# schematic.net
KiCad netlist of a schematic drawn in Altium Designer
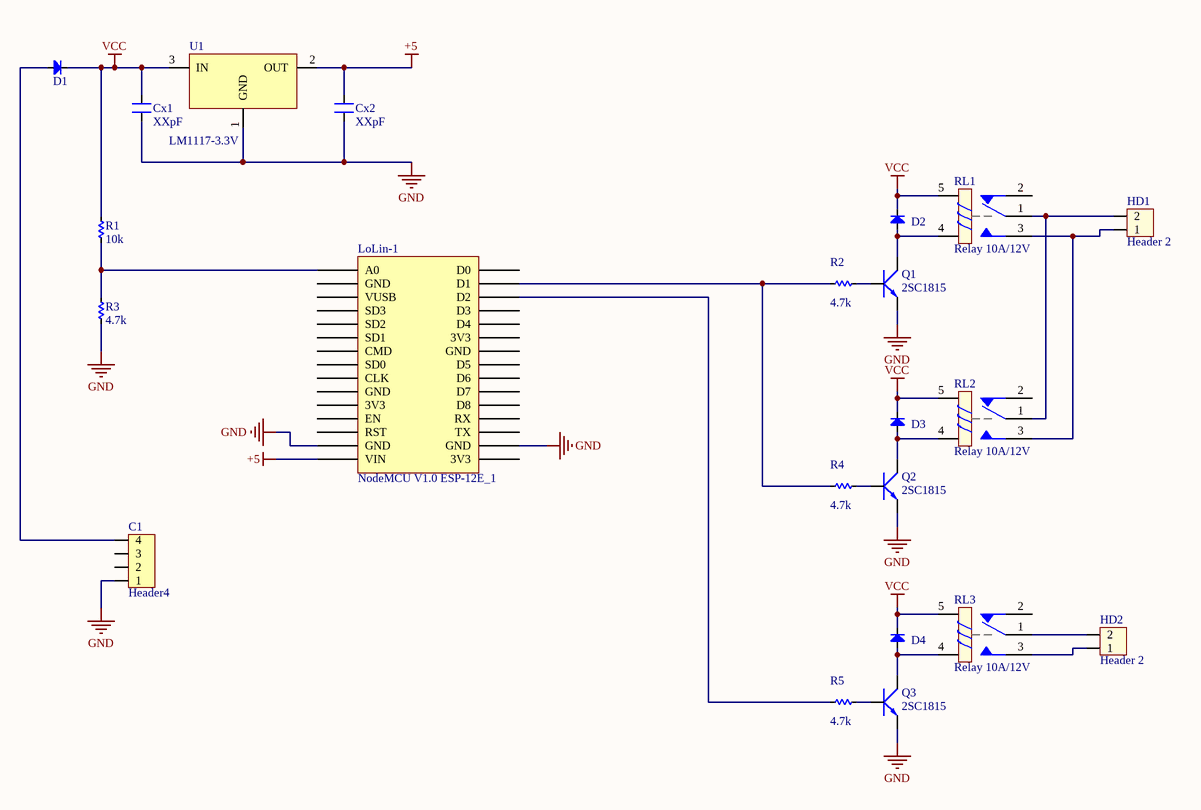
[diagram p0: schematic.SchDoc]

(export (version "E")
  (design (tool "Eeschema 10.0.6"))
  (components
    (comp (ref "C1")
      (value "Header4")
      (footprint "Header4")
      (description "Header IDC, 4 x 1 Pin Vertical 2.54mm Pitch (Non-Boxed, Male)")
      (fields
        (field (name "MANUFACTURER") "Würth Elektronik eiSos GmbH")
        (field (name "PARTNO") "613002143121")
        (field (name "CREATED BY") "Karrer Zheng")
      )
      (libsource (lib "LIBRARY") (part "Header4"))
    )
    (comp (ref "Cx1") (value "XXpF") (footprint "CN-SMD-1206") (libsource (lib "LIBRARY") (part "CN")))
    (comp (ref "Cx2") (value "XXpF") (footprint "CN-SMD-1206") (libsource (lib "LIBRARY") (part "CN")))
    (comp (ref "D1")
      (value "Diode")
      (footprint "DIO-1A-SMALL")
      (description "Default Diode")
      (fields (field (name "PUBLISHER") "Altium Limited"))
      (libsource (lib "LIBRARY") (part "Diode"))
    )
    (comp (ref "D2")
      (value "Diode")
      (footprint "DIO-1A-SMALL")
      (description "Default Diode")
      (fields (field (name "PUBLISHER") "Altium Limited"))
      (libsource (lib "LIBRARY") (part "Diode"))
    )
    (comp (ref "D3")
      (value "Diode")
      (footprint "DIO-1A-SMALL")
      (description "Default Diode")
      (fields (field (name "PUBLISHER") "Altium Limited"))
      (libsource (lib "LIBRARY") (part "Diode"))
    )
    (comp (ref "D4")
      (value "Diode")
      (footprint "DIO-1A-SMALL")
      (description "Default Diode")
      (fields (field (name "PUBLISHER") "Altium Limited"))
      (libsource (lib "LIBRARY") (part "Diode"))
    )
    (comp (ref "HD1")
      (value "Header 2")
      (footprint "HED2")
      (description "Header 2 (Green)")
      (libsource (lib "syhaunguyen") (part "Hed2"))
    )
    (comp (ref "HD2")
      (value "Header 2")
      (footprint "HED2")
      (description "Header 2 (Green)")
      (libsource (lib "syhaunguyen") (part "Hed2"))
    )
    (comp (ref "LoLin-1")
      (value "NodeMCU V1.0 ESP-12E_1")
      (footprint "LoLin NodeMcu V3")
      (description "LoLin NodeMCU V3")
      (libsource (lib "nodemcu") (part "NodeMCU V1.0 ESP-12E_1"))
    )
    (comp (ref "Q1")
      (value "2SC1815")
      (footprint "TO92-123")
      (description "NPN 600mW, ECB")
      (libsource (lib "LIBRARY") (part "2SC1815"))
    )
    (comp (ref "Q2")
      (value "2SC1815")
      (footprint "TO92-123")
      (description "NPN 600mW, ECB")
      (libsource (lib "LIBRARY") (part "2SC1815"))
    )
    (comp (ref "Q3")
      (value "2SC1815")
      (footprint "TO92-123")
      (description "NPN 600mW, ECB")
      (libsource (lib "LIBRARY") (part "2SC1815"))
    )
    (comp (ref "R1")
      (value "10k")
      (footprint "RES-1/4W-SMALL")
      (description "Res")
      (fields
        (field (name "MANUFACTURER") "Generic Components")
        (field (name "PUBLISHER") "Altium Hobart Technology Centre")
      )
      (libsource (lib "LIBRARY") (part "Res"))
    )
    (comp (ref "R2")
      (value "4.7k")
      (footprint "RES-1/4W-SMALL")
      (description "Res")
      (fields
        (field (name "MANUFACTURER") "Generic Components")
        (field (name "PUBLISHER") "Altium Hobart Technology Centre")
      )
      (libsource (lib "LIBRARY") (part "Res"))
    )
    (comp (ref "R3")
      (value "4.7k")
      (footprint "RES-1/4W-SMALL")
      (description "Res")
      (fields
        (field (name "MANUFACTURER") "Generic Components")
        (field (name "PUBLISHER") "Altium Hobart Technology Centre")
      )
      (libsource (lib "LIBRARY") (part "Res"))
    )
    (comp (ref "R4")
      (value "4.7k")
      (footprint "RES-1/4W-SMALL")
      (description "Res")
      (fields
        (field (name "MANUFACTURER") "Generic Components")
        (field (name "PUBLISHER") "Altium Hobart Technology Centre")
      )
      (libsource (lib "LIBRARY") (part "Res"))
    )
    (comp (ref "R5")
      (value "4.7k")
      (footprint "RES-1/4W-SMALL")
      (description "Res")
      (fields
        (field (name "MANUFACTURER") "Generic Components")
        (field (name "PUBLISHER") "Altium Hobart Technology Centre")
      )
      (libsource (lib "LIBRARY") (part "Res"))
    )
    (comp (ref "RL1")
      (value "Relay 10A/12V")
      (footprint "RELAY 5")
      (description "Relay SPDT,10A - 12VDC 5 Pin")
      (libsource (lib "LIBRARY") (part "Relay 5"))
    )
    (comp (ref "RL2")
      (value "Relay 10A/12V")
      (footprint "RELAY 5")
      (description "Relay SPDT,10A - 12VDC 5 Pin")
      (libsource (lib "LIBRARY") (part "Relay 5"))
    )
    (comp (ref "RL3")
      (value "Relay 10A/12V")
      (footprint "RELAY 5")
      (description "Relay SPDT,10A - 12VDC 5 Pin")
      (libsource (lib "LIBRARY") (part "Relay 5"))
    )
    (comp (ref "U1")
      (value "LM1117-3.3V")
      (footprint "SOT223")
      (description "800mA Low-Dropout Linear Regulator")
      (fields (field (name "CREATOR") "Nguyen Ba Bien"))
      (libsource (lib "LIBRARY") (part "LM1117"))
    )
  )
  (nets
    (net (code "1") (name "+5") (class "Default")
      (node (ref "Cx2") (pin "2") (pinfunction "2_2") (pintype "passive"))
      (node (ref "LoLin-1") (pin "VIN") (pinfunction "VIN_VIN") (pintype "passive"))
      (node (ref "U1") (pin "2") (pinfunction "OUT_2") (pintype "passive"))
    )
    (net (code "2") (name "GND") (class "Default")
      (node (ref "C1") (pin "1") (pinfunction "1_1") (pintype "passive"))
      (node (ref "Cx1") (pin "1") (pinfunction "1_1") (pintype "passive"))
      (node (ref "Cx2") (pin "1") (pinfunction "1_1") (pintype "passive"))
      (node (ref "LoLin-1") (pin "GND") (pinfunction "GND_GND") (pintype "passive"))
      (node (ref "Q1") (pin "1") (pinfunction "E_1") (pintype "passive"))
      (node (ref "Q2") (pin "1") (pinfunction "E_1") (pintype "passive"))
      (node (ref "Q3") (pin "1") (pinfunction "E_1") (pintype "passive"))
      (node (ref "R3") (pin "2") (pinfunction "2_2") (pintype "passive"))
      (node (ref "U1") (pin "1") (pinfunction "GND_1") (pintype "passive"))
    )
    (net (code "3") (name "Net-(D1-A)") (class "Default")
      (node (ref "C1") (pin "4") (pinfunction "4_4") (pintype "passive"))
      (node (ref "D1") (pin "1") (pinfunction "A_1") (pintype "passive"))
    )
    (net (code "4") (name "Net-(D2-A)") (class "Default")
      (node (ref "D2") (pin "1") (pinfunction "A_1") (pintype "passive"))
      (node (ref "Q1") (pin "2") (pinfunction "C_2") (pintype "passive"))
      (node (ref "RL1") (pin "4") (pinfunction "4_4") (pintype "passive"))
    )
    (net (code "5") (name "Net-(D3-A)") (class "Default")
      (node (ref "D3") (pin "1") (pinfunction "A_1") (pintype "passive"))
      (node (ref "Q2") (pin "2") (pinfunction "C_2") (pintype "passive"))
      (node (ref "RL2") (pin "4") (pinfunction "4_4") (pintype "passive"))
    )
    (net (code "6") (name "Net-(D4-A)") (class "Default")
      (node (ref "D4") (pin "1") (pinfunction "A_1") (pintype "passive"))
      (node (ref "Q3") (pin "2") (pinfunction "C_2") (pintype "passive"))
      (node (ref "RL3") (pin "4") (pinfunction "4_4") (pintype "passive"))
    )
    (net (code "7") (name "Net-(HD1-Pad1)") (class "Default")
      (node (ref "HD1") (pin "1") (pinfunction "1_1") (pintype "passive"))
      (node (ref "RL1") (pin "3") (pinfunction "3_3") (pintype "passive"))
      (node (ref "RL2") (pin "3") (pinfunction "3_3") (pintype "passive"))
    )
    (net (code "8") (name "Net-(HD1-Pad2)") (class "Default")
      (node (ref "HD1") (pin "2") (pinfunction "2_2") (pintype "passive"))
      (node (ref "RL1") (pin "1") (pinfunction "1_1") (pintype "passive"))
      (node (ref "RL2") (pin "1") (pinfunction "1_1") (pintype "passive"))
    )
    (net (code "9") (name "Net-(HD2-Pad1)") (class "Default")
      (node (ref "HD2") (pin "1") (pinfunction "1_1") (pintype "passive"))
      (node (ref "RL3") (pin "3") (pinfunction "3_3") (pintype "passive"))
    )
    (net (code "10") (name "Net-(HD2-Pad2)") (class "Default")
      (node (ref "HD2") (pin "2") (pinfunction "2_2") (pintype "passive"))
      (node (ref "RL3") (pin "1") (pinfunction "1_1") (pintype "passive"))
    )
    (net (code "11") (name "Net-(LoLin-1-PadA0)") (class "Default")
      (node (ref "LoLin-1") (pin "A0") (pinfunction "A0_A0") (pintype "passive"))
      (node (ref "R1") (pin "2") (pinfunction "2_2") (pintype "passive"))
      (node (ref "R3") (pin "1") (pinfunction "1_1") (pintype "passive"))
    )
    (net (code "12") (name "Net-(LoLin-1-PadD1)") (class "Default")
      (node (ref "LoLin-1") (pin "D1") (pinfunction "D1_D1") (pintype "passive"))
      (node (ref "R2") (pin "2") (pinfunction "2_2") (pintype "passive"))
      (node (ref "R4") (pin "2") (pinfunction "2_2") (pintype "passive"))
    )
    (net (code "13") (name "Net-(LoLin-1-PadD2)") (class "Default")
      (node (ref "LoLin-1") (pin "D2") (pinfunction "D2_D2") (pintype "passive"))
      (node (ref "R5") (pin "2") (pinfunction "2_2") (pintype "passive"))
    )
    (net (code "14") (name "Net-(Q1-B)") (class "Default")
      (node (ref "Q1") (pin "3") (pinfunction "B_3") (pintype "passive"))
      (node (ref "R2") (pin "1") (pinfunction "1_1") (pintype "passive"))
    )
    (net (code "15") (name "Net-(Q2-B)") (class "Default")
      (node (ref "Q2") (pin "3") (pinfunction "B_3") (pintype "passive"))
      (node (ref "R4") (pin "1") (pinfunction "1_1") (pintype "passive"))
    )
    (net (code "16") (name "Net-(Q3-B)") (class "Default")
      (node (ref "Q3") (pin "3") (pinfunction "B_3") (pintype "passive"))
      (node (ref "R5") (pin "1") (pinfunction "1_1") (pintype "passive"))
    )
    (net (code "17") (name "VCC") (class "Default")
      (node (ref "Cx1") (pin "2") (pinfunction "2_2") (pintype "passive"))
      (node (ref "D1") (pin "2") (pinfunction "K_2") (pintype "passive"))
      (node (ref "D2") (pin "2") (pinfunction "K_2") (pintype "passive"))
      (node (ref "D3") (pin "2") (pinfunction "K_2") (pintype "passive"))
      (node (ref "D4") (pin "2") (pinfunction "K_2") (pintype "passive"))
      (node (ref "R1") (pin "1") (pinfunction "1_1") (pintype "passive"))
      (node (ref "RL1") (pin "5") (pinfunction "5_5") (pintype "passive"))
      (node (ref "RL2") (pin "5") (pinfunction "5_5") (pintype "passive"))
      (node (ref "RL3") (pin "5") (pinfunction "5_5") (pintype "passive"))
      (node (ref "U1") (pin "3") (pinfunction "IN_3") (pintype "passive"))
    )
    (net (code "18") (name "unconnected-(C1-Pad2)") (class "Default")
      (node (ref "C1") (pin "2") (pinfunction "2_2") (pintype "passive"))
    )
    (net (code "19") (name "unconnected-(C1-Pad3)") (class "Default")
      (node (ref "C1") (pin "3") (pinfunction "3_3") (pintype "passive"))
    )
    (net (code "20") (name "unconnected-(LoLin-1-Pad3V3)") (class "Default")
      (node (ref "LoLin-1") (pin "3V3") (pinfunction "3V3_3V3") (pintype "passive"))
    )
    (net (code "21") (name "unconnected-(LoLin-1-Pad3V3)_1") (class "Default")
      (node (ref "LoLin-1") (pin "3V3") (pinfunction "3V3_3V3") (pintype "passive"))
    )
    (net (code "22") (name "unconnected-(LoLin-1-Pad3V3)_2") (class "Default")
      (node (ref "LoLin-1") (pin "3V3") (pinfunction "3V3_3V3") (pintype "passive"))
    )
    (net (code "23") (name "unconnected-(LoLin-1-PadCLK)") (class "Default")
      (node (ref "LoLin-1") (pin "CLK") (pinfunction "CLK_CLK") (pintype "passive"))
    )
    (net (code "24") (name "unconnected-(LoLin-1-PadCMD)") (class "Default")
      (node (ref "LoLin-1") (pin "CMD") (pinfunction "CMD_CMD") (pintype "passive"))
    )
    (net (code "25") (name "unconnected-(LoLin-1-PadD0)") (class "Default")
      (node (ref "LoLin-1") (pin "D0") (pinfunction "D0_D0") (pintype "passive"))
    )
    (net (code "26") (name "unconnected-(LoLin-1-PadD3)") (class "Default")
      (node (ref "LoLin-1") (pin "D3") (pinfunction "D3_D3") (pintype "passive"))
    )
    (net (code "27") (name "unconnected-(LoLin-1-PadD4)") (class "Default")
      (node (ref "LoLin-1") (pin "D4") (pinfunction "D4_D4") (pintype "passive"))
    )
    (net (code "28") (name "unconnected-(LoLin-1-PadD5)") (class "Default")
      (node (ref "LoLin-1") (pin "D5") (pinfunction "D5_D5") (pintype "passive"))
    )
    (net (code "29") (name "unconnected-(LoLin-1-PadD6)") (class "Default")
      (node (ref "LoLin-1") (pin "D6") (pinfunction "D6_D6") (pintype "passive"))
    )
    (net (code "30") (name "unconnected-(LoLin-1-PadD7)") (class "Default")
      (node (ref "LoLin-1") (pin "D7") (pinfunction "D7_D7") (pintype "passive"))
    )
    (net (code "31") (name "unconnected-(LoLin-1-PadD8)") (class "Default")
      (node (ref "LoLin-1") (pin "D8") (pinfunction "D8_D8") (pintype "passive"))
    )
    (net (code "32") (name "unconnected-(LoLin-1-PadEN)") (class "Default")
      (node (ref "LoLin-1") (pin "EN") (pinfunction "EN_EN") (pintype "passive"))
    )
    (net (code "33") (name "unconnected-(LoLin-1-PadGND)") (class "Default")
      (node (ref "LoLin-1") (pin "GND") (pinfunction "GND_GND") (pintype "passive"))
    )
    (net (code "34") (name "unconnected-(LoLin-1-PadGND)_1") (class "Default")
      (node (ref "LoLin-1") (pin "GND") (pinfunction "GND_GND") (pintype "passive"))
    )
    (net (code "35") (name "unconnected-(LoLin-1-PadGND)_2") (class "Default")
      (node (ref "LoLin-1") (pin "GND") (pinfunction "GND_GND") (pintype "passive"))
    )
    (net (code "36") (name "unconnected-(LoLin-1-PadRST)") (class "Default")
      (node (ref "LoLin-1") (pin "RST") (pinfunction "RST_RST") (pintype "passive"))
    )
    (net (code "37") (name "unconnected-(LoLin-1-PadRX)") (class "Default")
      (node (ref "LoLin-1") (pin "RX") (pinfunction "RX_RX") (pintype "passive"))
    )
    (net (code "38") (name "unconnected-(LoLin-1-PadSD0)") (class "Default")
      (node (ref "LoLin-1") (pin "SD0") (pinfunction "SD0_SD0") (pintype "passive"))
    )
    (net (code "39") (name "unconnected-(LoLin-1-PadSD1)") (class "Default")
      (node (ref "LoLin-1") (pin "SD1") (pinfunction "SD1_SD1") (pintype "passive"))
    )
    (net (code "40") (name "unconnected-(LoLin-1-PadSD2)") (class "Default")
      (node (ref "LoLin-1") (pin "SD2") (pinfunction "SD2_SD2") (pintype "passive"))
    )
    (net (code "41") (name "unconnected-(LoLin-1-PadSD3)") (class "Default")
      (node (ref "LoLin-1") (pin "SD3") (pinfunction "SD3_SD3") (pintype "passive"))
    )
    (net (code "42") (name "unconnected-(LoLin-1-PadTX)") (class "Default")
      (node (ref "LoLin-1") (pin "TX") (pinfunction "TX_TX") (pintype "passive"))
    )
    (net (code "43") (name "unconnected-(LoLin-1-PadVUSB)") (class "Default")
      (node (ref "LoLin-1") (pin "VUSB") (pinfunction "VUSB_VUSB") (pintype "passive"))
    )
    (net (code "44") (name "unconnected-(RL1-Pad2)") (class "Default")
      (node (ref "RL1") (pin "2") (pinfunction "2_2") (pintype "passive"))
    )
    (net (code "45") (name "unconnected-(RL2-Pad2)") (class "Default")
      (node (ref "RL2") (pin "2") (pinfunction "2_2") (pintype "passive"))
    )
    (net (code "46") (name "unconnected-(RL3-Pad2)") (class "Default")
      (node (ref "RL3") (pin "2") (pinfunction "2_2") (pintype "passive"))
    )
  )
)
